# ControllerBoardSchematic.net
KiCad netlist of a schematic drawn in Altium Designer
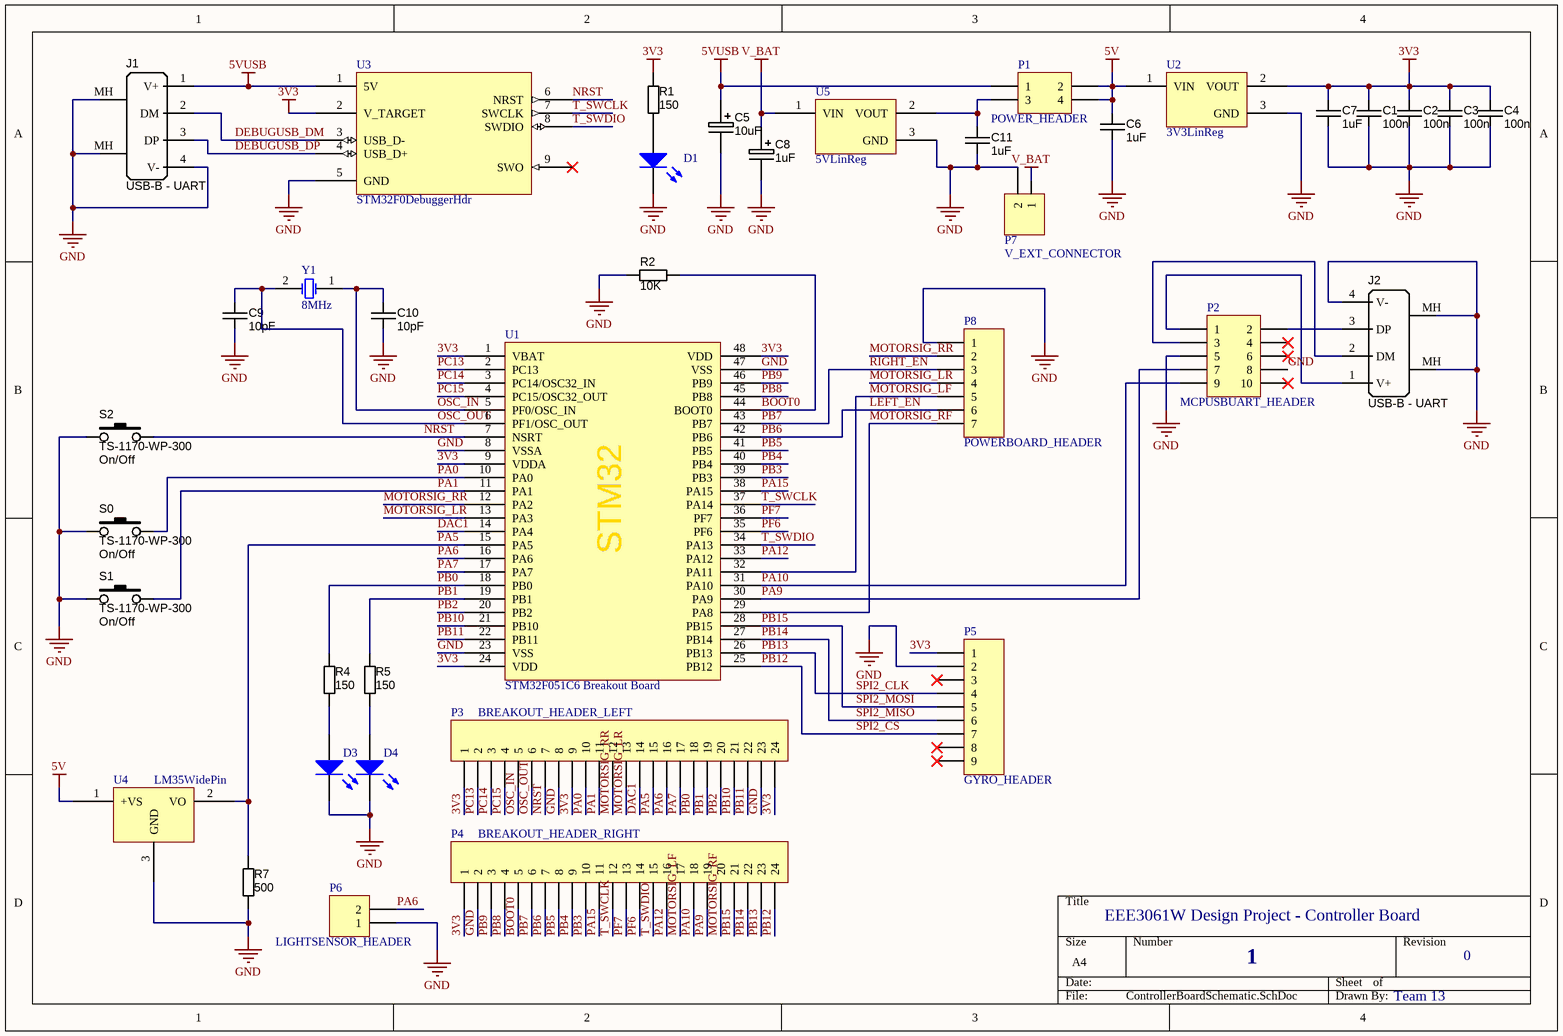
[diagram p0: ControllerBoardSchematic.SchDoc]

(export (version "E")
  (design (tool "Eeschema 10.0.6"))
  (components
    (comp (ref "C1")
      (value "100n")
      (footprint "CAPC500P450250X550_2.5mm")
      (description "Capacitor Ceramic 220nF 10% 50V X7R radial 5mm lead spacing")
      (fields (field (name "TOLERANCE") "±10%"))
      (libsource (lib "PBL - Capacitors") (part "CAPR_220n_Radial_5mm"))
    )
    (comp (ref "C2")
      (value "100n")
      (footprint "CAPC500P450250X550_2.5mm")
      (description "Capacitor Ceramic 220nF 10% 50V X7R radial 5mm lead spacing")
      (fields (field (name "TOLERANCE") "±10%"))
      (libsource (lib "PBL - Capacitors") (part "CAPR_220n_Radial_5mm"))
    )
    (comp (ref "C3")
      (value "100n")
      (footprint "CAPC500P450250X550_2.5mm")
      (description "Capacitor Ceramic 220nF 10% 50V X7R radial 5mm lead spacing")
      (fields (field (name "TOLERANCE") "±10%"))
      (libsource (lib "PBL - Capacitors") (part "CAPR_220n_Radial_5mm"))
    )
    (comp (ref "C4")
      (value "100n")
      (footprint "CAPC500P450250X550_2.5mm")
      (description "Capacitor Ceramic 220nF 10% 50V X7R radial 5mm lead spacing")
      (fields (field (name "TOLERANCE") "±10%"))
      (libsource (lib "PBL - Capacitors") (part "CAPR_220n_Radial_5mm"))
    )
    (comp (ref "C5")
      (value "10uF")
      (footprint "CAPE10.0MM_Rad_10x14mm")
      (description "Capacitor THT Alum Elec 470uF 20% 16V")
      (fields (field (name "TOLERANCE") "±20%"))
      (libsource (lib "PBL - Capacitors") (part "CAPE_470u_16V_THT"))
    )
    (comp (ref "C6")
      (value "1uF")
      (footprint "CAPC500P450250X550_2.5mm")
      (description "Capacitor Ceramic 220nF 10% 50V X7R radial 5mm lead spacing")
      (fields (field (name "TOLERANCE") "±10%"))
      (libsource (lib "PBL - Capacitors") (part "CAPR_220n_Radial_5mm"))
    )
    (comp (ref "C7")
      (value "1uF")
      (footprint "CAPC500P450250X550_2.5mm")
      (description "Capacitor Ceramic 220nF 10% 50V X7R radial 5mm lead spacing")
      (fields (field (name "TOLERANCE") "±10%"))
      (libsource (lib "PBL - Capacitors") (part "CAPR_220n_Radial_5mm"))
    )
    (comp (ref "C8")
      (value "1uF")
      (footprint "CAPE10.0MM_Rad_10x14mm")
      (description "Capacitor THT Alum Elec 470uF 20% 16V")
      (fields (field (name "TOLERANCE") "±20%"))
      (libsource (lib "PBL - Capacitors") (part "CAPE_470u_16V_THT"))
    )
    (comp (ref "C9")
      (value "10pF")
      (footprint "CAPC500P450250X550_2.5mm")
      (description "Capacitor Ceramic 220nF 10% 50V X7R radial 5mm lead spacing")
      (fields (field (name "TOLERANCE") "±10%"))
      (libsource (lib "PBL - Capacitors") (part "CAPR_220n_Radial_5mm"))
    )
    (comp (ref "C10")
      (value "10pF")
      (footprint "CAPC500P450250X550_2.5mm")
      (description "Capacitor Ceramic 220nF 10% 50V X7R radial 5mm lead spacing")
      (fields (field (name "TOLERANCE") "±10%"))
      (libsource (lib "PBL - Capacitors") (part "CAPR_220n_Radial_5mm"))
    )
    (comp (ref "C11")
      (value "1uF")
      (footprint "CAPC500P450250X550_2.5mm")
      (description "Capacitor Ceramic 220nF 10% 50V X7R radial 5mm lead spacing")
      (fields (field (name "TOLERANCE") "±10%"))
      (libsource (lib "PBL - Capacitors") (part "CAPR_220n_Radial_5mm"))
    )
    (comp (ref "D1")
      (value "LED1")
      (footprint "LED-1")
      (description "Typical RED GaAs LED")
      (fields (field (name "PUBLISHER") "Altium Limited"))
      (libsource (lib "Miscellaneous Devices") (part "LED1"))
    )
    (comp (ref "D3")
      (value "LED1")
      (footprint "LED-1")
      (description "Typical RED GaAs LED")
      (fields (field (name "PUBLISHER") "Altium Limited"))
      (libsource (lib "Miscellaneous Devices") (part "LED1"))
    )
    (comp (ref "D4")
      (value "LED1")
      (footprint "LED-1")
      (description "Typical RED GaAs LED")
      (fields (field (name "PUBLISHER") "Altium Limited"))
      (libsource (lib "Miscellaneous Devices") (part "LED1"))
    )
    (comp (ref "J1")
      (value "USB-B - UART")
      (footprint "USB_TypeB_Tyco")
      (description "Connector THT Type B USB connector")
      (libsource (lib "PBL - Connectors") (part "USB_TypeB"))
    )
    (comp (ref "J2")
      (value "USB-B - UART")
      (footprint "USB_TypeB_Tyco")
      (description "Connector THT Type B USB connector")
      (libsource (lib "PBL - Connectors") (part "USB_TypeB"))
    )
    (comp (ref "P1")
      (value "POWER_HEADER")
      (footprint "HDR2X2")
      (description "Header, 2-Pin, Dual row")
      (fields (field (name "PUBLISHER") "Altium Limited"))
      (libsource (lib "Miscellaneous Connectors") (part "Header 2X2"))
    )
    (comp (ref "P2")
      (value "MCPUSBUART_HEADER")
      (footprint "HDR2X5")
      (description "Header, 5-Pin, Dual row")
      (fields (field (name "PUBLISHER") "Altium Limited"))
      (libsource (lib "Miscellaneous Connectors") (part "Header 5X2"))
    )
    (comp (ref "P3")
      (value "BREAKOUT_HEADER_LEFT")
      (footprint "HDR1X24")
      (description "Header, 24-Pin")
      (fields (field (name "PUBLISHER") "Altium Limited"))
      (libsource (lib "Miscellaneous Connectors") (part "Header 24"))
    )
    (comp (ref "P4")
      (value "BREAKOUT_HEADER_RIGHT")
      (footprint "HDR1X24")
      (description "Header, 24-Pin")
      (fields (field (name "PUBLISHER") "Altium Limited"))
      (libsource (lib "Miscellaneous Connectors") (part "Header 24"))
    )
    (comp (ref "P5")
      (value "GYRO_HEADER")
      (footprint "HDR1X9")
      (description "Header, 9-Pin")
      (fields (field (name "PUBLISHER") "Altium Limited"))
      (libsource (lib "Miscellaneous Connectors") (part "Header 9"))
    )
    (comp (ref "P6")
      (value "LIGHTSENSOR_HEADER")
      (footprint "HDR1X2")
      (description "Header, 2-Pin")
      (fields (field (name "PUBLISHER") "Altium Limited"))
      (libsource (lib "") (part "Header 2_1"))
    )
    (comp (ref "P7")
      (value "V_EXT_CONNECTOR")
      (footprint "HDR1X2")
      (description "Header, 2-Pin")
      (fields (field (name "PUBLISHER") "Altium Limited"))
      (libsource (lib "Miscellaneous Connectors") (part "Header 2"))
    )
    (comp (ref "P8")
      (value "POWERBOARD_HEADER")
      (footprint "HDR1X7")
      (description "Header, 7-Pin")
      (fields (field (name "PUBLISHER") "Altium Limited"))
      (libsource (lib "Miscellaneous Connectors") (part "Header 7"))
    )
    (comp (ref "R1")
      (value "150")
      (footprint "RESTH_AXIAL-0.4")
      (description "Resistor THD Axial 1k Ohm 0.25W 5% Carbon Film")
      (fields (field (name "TOLERANCE") "±5%") (field (name "Comment") "Carbon Film"))
      (libsource (lib "PBL - Resistors") (part "RES_1K_Axial_0.25W_5%"))
    )
    (comp (ref "R2")
      (value "10K")
      (footprint "RESTH_AXIAL-0.4")
      (description "Resistor THD Axial 1k Ohm 0.25W 5% Carbon Film")
      (fields (field (name "TOLERANCE") "±5%") (field (name "Comment") "Carbon Film"))
      (libsource (lib "") (part "RES_1K_Axial_0.25W_5%_2"))
    )
    (comp (ref "R4")
      (value "150")
      (footprint "RESTH_AXIAL-0.4")
      (description "Resistor THD Axial 1k Ohm 0.25W 5% Carbon Film")
      (fields (field (name "TOLERANCE") "±5%") (field (name "Comment") "Carbon Film"))
      (libsource (lib "") (part "RES_1K_Axial_0.25W_5%_1"))
    )
    (comp (ref "R5")
      (value "150")
      (footprint "RESTH_AXIAL-0.4")
      (description "Resistor THD Axial 1k Ohm 0.25W 5% Carbon Film")
      (fields (field (name "TOLERANCE") "±5%") (field (name "Comment") "Carbon Film"))
      (libsource (lib "") (part "RES_1K_Axial_0.25W_5%_1"))
    )
    (comp (ref "R7")
      (value "500")
      (footprint "RESTH_AXIAL-0.4")
      (description "Resistor THD Axial 1k Ohm 0.25W 5% Carbon Film")
      (fields (field (name "TOLERANCE") "±5%") (field (name "Comment") "Carbon Film"))
      (libsource (lib "") (part "RES_1K_Axial_0.25W_5%_1"))
    )
    (comp (ref "S0")
      (value "SW_THT_PB_7.0mm")
      (footprint "TACT-SWITCH-TS1170")
      (description "Switch, tact, 7.0mm stem")
      (fields (field (name "MANUFACTURER PART NUMBER 1") "TS-1170-WP-300") (field (name "FUNCTION") "On/Off"))
      (libsource (lib "PBL - Switches") (part "SW_THT_PB_7.0mm"))
    )
    (comp (ref "S1")
      (value "SW_THT_PB_7.0mm")
      (footprint "TACT-SWITCH-TS1170")
      (description "Switch, tact, 7.0mm stem")
      (fields (field (name "MANUFACTURER PART NUMBER 1") "TS-1170-WP-300") (field (name "FUNCTION") "On/Off"))
      (libsource (lib "PBL - Switches") (part "SW_THT_PB_7.0mm"))
    )
    (comp (ref "S2")
      (value "SW_THT_PB_7.0mm")
      (footprint "TACT-SWITCH-TS1170")
      (description "Switch, tact, 7.0mm stem")
      (fields (field (name "MANUFACTURER PART NUMBER 1") "TS-1170-WP-300") (field (name "FUNCTION") "On/Off"))
      (libsource (lib "PBL - Switches") (part "SW_THT_PB_7.0mm"))
    )
    (comp (ref "U1")
      (value "STM32F051C6 Breakout Board")
      (footprint "STM32F051C6BreakoutBoard")
      (libsource (lib "STM32F051C6Breakout") (part "STM32F051C6Brk"))
    )
    (comp (ref "U2")
      (value "3V3LinReg")
      (footprint "TO-92Wide")
      (description "MCP")
      (libsource (lib "STM32F051C6Breakout") (part "VREG5V"))
    )
    (comp (ref "U3")
      (value "STM32F0DebuggerHdr")
      (footprint "STM32F051C6_DbgrHdr")
      (libsource (lib "STM32F051C6Breakout") (part "STM32F0DebuggerHdr"))
    )
    (comp (ref "U4")
      (value "LM35WidePin")
      (footprint "TO-92Wide")
      (libsource (lib "STM32F051C6Breakout") (part "LM35Big"))
    )
    (comp (ref "U5")
      (value "5VLinReg")
      (footprint "TO-92Wide")
      (description "MCP")
      (libsource (lib "STM32F051C6Breakout") (part "VREG5V"))
    )
    (comp (ref "Y1")
      (value "8MHz")
      (footprint "8MHZOSC")
      (description "Crystal Oscillator")
      (fields (field (name "PUBLISHER") "Altium Limited"))
      (libsource (lib "Miscellaneous Devices") (part "XTAL"))
    )
  )
  (nets
    (net (code "1") (name "/BOOT0") (class "Default")
      (node (ref "P4") (pin "5") (pinfunction "5_5") (pintype "passive"))
      (node (ref "R2") (pin "2") (pinfunction "2_2") (pintype "passive"))
      (node (ref "U1") (pin "44") (pinfunction "BOOT0_44") (pintype "passive"))
    )
    (net (code "2") (name "/DAC1") (class "Default")
      (node (ref "P3") (pin "14") (pinfunction "14_14") (pintype "passive"))
      (node (ref "U1") (pin "14") (pinfunction "PA4_14") (pintype "passive"))
    )
    (net (code "3") (name "/DEBUGUSB_DM") (class "Default")
      (node (ref "J1") (pin "2") (pinfunction "DM_2") (pintype "passive"))
      (node (ref "U3") (pin "3") (pinfunction "USB_D-_3") (pintype "bidirectional"))
    )
    (net (code "4") (name "/DEBUGUSB_DP") (class "Default")
      (node (ref "J1") (pin "3") (pinfunction "DP_3") (pintype "passive"))
      (node (ref "U3") (pin "4") (pinfunction "USB_D+_4") (pintype "bidirectional"))
    )
    (net (code "5") (name "/LEFT_EN") (class "Default")
      (node (ref "P4") (pin "7") (pinfunction "7_7") (pintype "passive"))
      (node (ref "P8") (pin "6") (pinfunction "6_6") (pintype "passive"))
      (node (ref "U1") (pin "42") (pinfunction "PB6_42") (pintype "passive"))
    )
    (net (code "6") (name "/MOTORSIG_LF") (class "Default")
      (node (ref "P4") (pin "17") (pinfunction "17_17") (pintype "passive"))
      (node (ref "P8") (pin "5") (pinfunction "5_5") (pintype "passive"))
      (node (ref "U1") (pin "32") (pinfunction "PA11_32") (pintype "passive"))
    )
    (net (code "7") (name "/MOTORSIG_LR") (class "Default")
      (node (ref "P3") (pin "13") (pinfunction "13_13") (pintype "passive"))
      (node (ref "P8") (pin "4") (pinfunction "4_4") (pintype "passive"))
      (node (ref "U1") (pin "13") (pinfunction "PA3_13") (pintype "passive"))
    )
    (net (code "8") (name "/MOTORSIG_RF") (class "Default")
      (node (ref "P4") (pin "20") (pinfunction "20_20") (pintype "passive"))
      (node (ref "P8") (pin "7") (pinfunction "7_7") (pintype "passive"))
      (node (ref "U1") (pin "29") (pinfunction "PA8_29") (pintype "passive"))
    )
    (net (code "9") (name "/MOTORSIG_RR") (class "Default")
      (node (ref "P3") (pin "12") (pinfunction "12_12") (pintype "passive"))
      (node (ref "P8") (pin "2") (pinfunction "2_2") (pintype "passive"))
      (node (ref "U1") (pin "12") (pinfunction "PA2_12") (pintype "passive"))
    )
    (net (code "10") (name "/NRST") (class "Default")
      (node (ref "P3") (pin "7") (pinfunction "7_7") (pintype "passive"))
      (node (ref "S2") (pin "2") (pintype "passive"))
      (node (ref "U1") (pin "7") (pinfunction "NSRT_7") (pintype "passive"))
      (node (ref "U3") (pin "6") (pinfunction "NRST_6") (pintype "output"))
    )
    (net (code "11") (name "/OSC_IN") (class "Default")
      (node (ref "C10") (pin "1") (pintype "passive"))
      (node (ref "P3") (pin "5") (pinfunction "5_5") (pintype "passive"))
      (node (ref "U1") (pin "5") (pinfunction "PF0/OSC_IN_5") (pintype "passive"))
      (node (ref "Y1") (pin "1") (pinfunction "OSC1_1") (pintype "passive"))
    )
    (net (code "12") (name "/OSC_OUT") (class "Default")
      (node (ref "C9") (pin "1") (pintype "passive"))
      (node (ref "P3") (pin "6") (pinfunction "6_6") (pintype "passive"))
      (node (ref "U1") (pin "6") (pinfunction "PF1/OSC_OUT_6") (pintype "passive"))
      (node (ref "Y1") (pin "2") (pinfunction "OSC2_2") (pintype "passive"))
    )
    (net (code "13") (name "/PA0") (class "Default")
      (node (ref "P3") (pin "10") (pinfunction "10_10") (pintype "passive"))
      (node (ref "S0") (pin "2") (pintype "passive"))
      (node (ref "U1") (pin "10") (pinfunction "PA0_10") (pintype "passive"))
    )
    (net (code "14") (name "/PA1") (class "Default")
      (node (ref "P3") (pin "11") (pinfunction "11_11") (pintype "passive"))
      (node (ref "S1") (pin "2") (pintype "passive"))
      (node (ref "U1") (pin "11") (pinfunction "PA1_11") (pintype "passive"))
    )
    (net (code "15") (name "/PA5") (class "Default")
      (node (ref "P3") (pin "15") (pinfunction "15_15") (pintype "passive"))
      (node (ref "R7") (pin "1") (pinfunction "1_1") (pintype "passive"))
      (node (ref "U1") (pin "15") (pinfunction "PA5_15") (pintype "passive"))
      (node (ref "U4") (pin "2") (pinfunction "VO_2") (pintype "passive"))
    )
    (net (code "16") (name "/PA6") (class "Default")
      (node (ref "P3") (pin "16") (pinfunction "16_16") (pintype "passive"))
      (node (ref "P6") (pin "2") (pinfunction "2_2") (pintype "passive"))
      (node (ref "U1") (pin "16") (pinfunction "PA6_16") (pintype "passive"))
    )
    (net (code "17") (name "/PA7") (class "Default")
      (node (ref "P3") (pin "17") (pinfunction "17_17") (pintype "passive"))
      (node (ref "U1") (pin "17") (pinfunction "PA7_17") (pintype "passive"))
    )
    (net (code "18") (name "/PA9") (class "Default")
      (node (ref "P2") (pin "7") (pinfunction "7_7") (pintype "passive"))
      (node (ref "P4") (pin "19") (pinfunction "19_19") (pintype "passive"))
      (node (ref "U1") (pin "30") (pinfunction "PA9_30") (pintype "passive"))
    )
    (net (code "19") (name "/PA10") (class "Default")
      (node (ref "P2") (pin "9") (pinfunction "9_9") (pintype "passive"))
      (node (ref "P4") (pin "18") (pinfunction "18_18") (pintype "passive"))
      (node (ref "U1") (pin "31") (pinfunction "PA10_31") (pintype "passive"))
    )
    (net (code "20") (name "/PA12") (class "Default")
      (node (ref "P4") (pin "16") (pinfunction "16_16") (pintype "passive"))
      (node (ref "U1") (pin "33") (pinfunction "PA12_33") (pintype "passive"))
    )
    (net (code "21") (name "/PA15") (class "Default")
      (node (ref "P4") (pin "11") (pinfunction "11_11") (pintype "passive"))
      (node (ref "U1") (pin "38") (pinfunction "PA15_38") (pintype "passive"))
    )
    (net (code "22") (name "/PB0") (class "Default")
      (node (ref "P3") (pin "18") (pinfunction "18_18") (pintype "passive"))
      (node (ref "R4") (pin "1") (pinfunction "1_1") (pintype "passive"))
      (node (ref "U1") (pin "18") (pinfunction "PB0_18") (pintype "passive"))
    )
    (net (code "23") (name "/PB1") (class "Default")
      (node (ref "P3") (pin "19") (pinfunction "19_19") (pintype "passive"))
      (node (ref "R5") (pin "1") (pinfunction "1_1") (pintype "passive"))
      (node (ref "U1") (pin "19") (pinfunction "PB1_19") (pintype "passive"))
    )
    (net (code "24") (name "/PB2") (class "Default")
      (node (ref "P3") (pin "20") (pinfunction "20_20") (pintype "passive"))
      (node (ref "U1") (pin "20") (pinfunction "PB2_20") (pintype "passive"))
    )
    (net (code "25") (name "/PB3") (class "Default")
      (node (ref "P4") (pin "10") (pinfunction "10_10") (pintype "passive"))
      (node (ref "U1") (pin "39") (pinfunction "PB3_39") (pintype "passive"))
    )
    (net (code "26") (name "/PB4") (class "Default")
      (node (ref "P4") (pin "9") (pinfunction "9_9") (pintype "passive"))
      (node (ref "U1") (pin "40") (pinfunction "PB4_40") (pintype "passive"))
    )
    (net (code "27") (name "/PB5") (class "Default")
      (node (ref "P4") (pin "8") (pinfunction "8_8") (pintype "passive"))
      (node (ref "U1") (pin "41") (pinfunction "PB5_41") (pintype "passive"))
    )
    (net (code "28") (name "/PB7") (class "Default")
      (node (ref "P4") (pin "6") (pinfunction "6_6") (pintype "passive"))
      (node (ref "P8") (pin "3") (pinfunction "3_3") (pintype "passive"))
      (node (ref "U1") (pin "43") (pinfunction "PB7_43") (pintype "passive"))
    )
    (net (code "29") (name "/PB8") (class "Default")
      (node (ref "P4") (pin "4") (pinfunction "4_4") (pintype "passive"))
      (node (ref "U1") (pin "45") (pinfunction "PB8_45") (pintype "passive"))
    )
    (net (code "30") (name "/PB9") (class "Default")
      (node (ref "P4") (pin "3") (pinfunction "3_3") (pintype "passive"))
      (node (ref "U1") (pin "46") (pinfunction "PB9_46") (pintype "passive"))
    )
    (net (code "31") (name "/PB10") (class "Default")
      (node (ref "P3") (pin "21") (pinfunction "21_21") (pintype "passive"))
      (node (ref "U1") (pin "21") (pinfunction "PB10_21") (pintype "passive"))
    )
    (net (code "32") (name "/PB11") (class "Default")
      (node (ref "P3") (pin "22") (pinfunction "22_22") (pintype "passive"))
      (node (ref "U1") (pin "22") (pinfunction "PB11_22") (pintype "passive"))
    )
    (net (code "33") (name "/PB12") (class "Default")
      (node (ref "P4") (pin "24") (pinfunction "24_24") (pintype "passive"))
      (node (ref "P5") (pin "7") (pinfunction "7_7") (pintype "passive"))
      (node (ref "U1") (pin "25") (pinfunction "PB12_25") (pintype "passive"))
    )
    (net (code "34") (name "/PB13") (class "Default")
      (node (ref "P4") (pin "23") (pinfunction "23_23") (pintype "passive"))
      (node (ref "P5") (pin "4") (pinfunction "4_4") (pintype "passive"))
      (node (ref "U1") (pin "26") (pinfunction "PB13_26") (pintype "passive"))
    )
    (net (code "35") (name "/PB14") (class "Default")
      (node (ref "P4") (pin "22") (pinfunction "22_22") (pintype "passive"))
      (node (ref "P5") (pin "6") (pinfunction "6_6") (pintype "passive"))
      (node (ref "U1") (pin "27") (pinfunction "PB14_27") (pintype "passive"))
    )
    (net (code "36") (name "/PB15") (class "Default")
      (node (ref "P4") (pin "21") (pinfunction "21_21") (pintype "passive"))
      (node (ref "P5") (pin "5") (pinfunction "5_5") (pintype "passive"))
      (node (ref "U1") (pin "28") (pinfunction "PB15_28") (pintype "passive"))
    )
    (net (code "37") (name "/PC13") (class "Default")
      (node (ref "P3") (pin "2") (pinfunction "2_2") (pintype "passive"))
      (node (ref "U1") (pin "2") (pinfunction "PC13_2") (pintype "passive"))
    )
    (net (code "38") (name "/PC14") (class "Default")
      (node (ref "P3") (pin "3") (pinfunction "3_3") (pintype "passive"))
      (node (ref "U1") (pin "3") (pinfunction "PC14/OSC32_IN_3") (pintype "passive"))
    )
    (net (code "39") (name "/PC15") (class "Default")
      (node (ref "P3") (pin "4") (pinfunction "4_4") (pintype "passive"))
      (node (ref "U1") (pin "4") (pinfunction "PC15/OSC32_OUT_4") (pintype "passive"))
    )
    (net (code "40") (name "/PF6") (class "Default")
      (node (ref "P4") (pin "14") (pinfunction "14_14") (pintype "passive"))
      (node (ref "U1") (pin "35") (pinfunction "PF6_35") (pintype "passive"))
    )
    (net (code "41") (name "/PF7") (class "Default")
      (node (ref "P4") (pin "13") (pinfunction "13_13") (pintype "passive"))
      (node (ref "U1") (pin "36") (pinfunction "PF7_36") (pintype "passive"))
    )
    (net (code "42") (name "/T_SWCLK") (class "Default")
      (node (ref "P4") (pin "12") (pinfunction "12_12") (pintype "passive"))
      (node (ref "U1") (pin "37") (pinfunction "PA14_37") (pintype "passive"))
      (node (ref "U3") (pin "7") (pinfunction "SWCLK_7") (pintype "output"))
    )
    (net (code "43") (name "/T_SWDIO") (class "Default")
      (node (ref "P4") (pin "15") (pinfunction "15_15") (pintype "passive"))
      (node (ref "U1") (pin "34") (pinfunction "PA13_34") (pintype "passive"))
      (node (ref "U3") (pin "8") (pinfunction "SWDIO_8") (pintype "bidirectional"))
    )
    (net (code "44") (name "3V3") (class "Default")
      (node (ref "C1") (pin "1") (pintype "passive"))
      (node (ref "C2") (pin "1") (pintype "passive"))
      (node (ref "C3") (pin "1") (pintype "passive"))
      (node (ref "C4") (pin "1") (pintype "passive"))
      (node (ref "C7") (pin "1") (pintype "passive"))
      (node (ref "P3") (pin "1") (pinfunction "1_1") (pintype "passive"))
      (node (ref "P3") (pin "24") (pinfunction "24_24") (pintype "passive"))
      (node (ref "P3") (pin "9") (pinfunction "9_9") (pintype "passive"))
      (node (ref "P4") (pin "1") (pinfunction "1_1") (pintype "passive"))
      (node (ref "P5") (pin "1") (pinfunction "1_1") (pintype "passive"))
      (node (ref "R1") (pin "2") (pinfunction "2_2") (pintype "passive"))
      (node (ref "U1") (pin "1") (pinfunction "VBAT_1") (pintype "passive"))
      (node (ref "U1") (pin "24") (pinfunction "VDD_24") (pintype "passive"))
      (node (ref "U1") (pin "48") (pinfunction "VDD_48") (pintype "passive"))
      (node (ref "U1") (pin "9") (pinfunction "VDDA_9") (pintype "passive"))
      (node (ref "U2") (pin "2") (pinfunction "VOUT_2") (pintype "passive"))
      (node (ref "U3") (pin "2") (pinfunction "V_TARGET_2") (pintype "passive"))
    )
    (net (code "45") (name "5V") (class "Default")
      (node (ref "C6") (pin "1") (pintype "passive"))
      (node (ref "P1") (pin "2") (pinfunction "2_2") (pintype "passive"))
      (node (ref "P1") (pin "4") (pinfunction "4_4") (pintype "passive"))
      (node (ref "U2") (pin "1") (pinfunction "VIN_1") (pintype "passive"))
      (node (ref "U4") (pin "1") (pinfunction "+VS_1") (pintype "passive"))
    )
    (net (code "46") (name "5VUSB") (class "Default")
      (node (ref "C5") (pin "1") (pintype "passive"))
      (node (ref "J1") (pin "1") (pinfunction "V+_1") (pintype "passive"))
      (node (ref "P1") (pin "1") (pinfunction "1_1") (pintype "passive"))
      (node (ref "U3") (pin "1") (pinfunction "5V_1") (pintype "passive"))
    )
    (net (code "47") (name "GND") (class "Default")
      (node (ref "C1") (pin "2") (pintype "passive"))
      (node (ref "C10") (pin "2") (pintype "passive"))
      (node (ref "C11") (pin "2") (pintype "passive"))
      (node (ref "C2") (pin "2") (pintype "passive"))
      (node (ref "C3") (pin "2") (pintype "passive"))
      (node (ref "C4") (pin "2") (pintype "passive"))
      (node (ref "C5") (pin "2") (pintype "passive"))
      (node (ref "C6") (pin "2") (pintype "passive"))
      (node (ref "C7") (pin "2") (pintype "passive"))
      (node (ref "C8") (pin "2") (pintype "passive"))
      (node (ref "C9") (pin "2") (pintype "passive"))
      (node (ref "D1") (pin "2") (pinfunction "K_2") (pintype "passive"))
      (node (ref "D3") (pin "2") (pinfunction "K_2") (pintype "passive"))
      (node (ref "D4") (pin "2") (pinfunction "K_2") (pintype "passive"))
      (node (ref "J1") (pin "4") (pinfunction "V-_4") (pintype "passive"))
      (node (ref "J1") (pin "MH") (pinfunction "Shell_MH") (pintype "passive"))
      (node (ref "J2") (pin "4") (pinfunction "V-_4") (pintype "passive"))
      (node (ref "J2") (pin "MH") (pinfunction "Shell_MH") (pintype "passive"))
      (node (ref "P2") (pin "5") (pinfunction "5_5") (pintype "passive"))
      (node (ref "P2") (pin "8") (pinfunction "8_8") (pintype "passive"))
      (node (ref "P3") (pin "23") (pinfunction "23_23") (pintype "passive"))
      (node (ref "P3") (pin "8") (pinfunction "8_8") (pintype "passive"))
      (node (ref "P4") (pin "2") (pinfunction "2_2") (pintype "passive"))
      (node (ref "P5") (pin "2") (pinfunction "2_2") (pintype "passive"))
      (node (ref "P6") (pin "1") (pinfunction "1_1") (pintype "passive"))
      (node (ref "P7") (pin "2") (pinfunction "2_2") (pintype "passive"))
      (node (ref "P8") (pin "1") (pinfunction "1_1") (pintype "passive"))
      (node (ref "R2") (pin "1") (pinfunction "1_1") (pintype "passive"))
      (node (ref "R7") (pin "2") (pinfunction "2_2") (pintype "passive"))
      (node (ref "S0") (pin "1") (pintype "passive"))
      (node (ref "S1") (pin "1") (pintype "passive"))
      (node (ref "S2") (pin "1") (pintype "passive"))
      (node (ref "U1") (pin "23") (pinfunction "VSS_23") (pintype "passive"))
      (node (ref "U1") (pin "47") (pinfunction "VSS_47") (pintype "passive"))
      (node (ref "U1") (pin "8") (pinfunction "VSSA_8") (pintype "passive"))
      (node (ref "U2") (pin "3") (pinfunction "GND_3") (pintype "passive"))
      (node (ref "U3") (pin "5") (pinfunction "GND_5") (pintype "passive"))
      (node (ref "U4") (pin "3") (pinfunction "GND_3") (pintype "passive"))
      (node (ref "U5") (pin "3") (pinfunction "GND_3") (pintype "passive"))
    )
    (net (code "48") (name "Net-(D1-A)") (class "Default")
      (node (ref "D1") (pin "1") (pinfunction "A_1") (pintype "passive"))
      (node (ref "R1") (pin "1") (pinfunction "1_1") (pintype "passive"))
    )
    (net (code "49") (name "Net-(D3-A)") (class "Default")
      (node (ref "D3") (pin "1") (pinfunction "A_1") (pintype "passive"))
      (node (ref "R4") (pin "2") (pinfunction "2_2") (pintype "passive"))
    )
    (net (code "50") (name "Net-(D4-A)") (class "Default")
      (node (ref "D4") (pin "1") (pinfunction "A_1") (pintype "passive"))
      (node (ref "R5") (pin "2") (pinfunction "2_2") (pintype "passive"))
    )
    (net (code "51") (name "Net-(J2-DM)") (class "Default")
      (node (ref "J2") (pin "2") (pinfunction "DM_2") (pintype "passive"))
      (node (ref "P2") (pin "3") (pinfunction "3_3") (pintype "passive"))
    )
    (net (code "52") (name "Net-(J2-DP)") (class "Default")
      (node (ref "J2") (pin "3") (pinfunction "DP_3") (pintype "passive"))
      (node (ref "P2") (pin "2") (pinfunction "2_2") (pintype "passive"))
    )
    (net (code "53") (name "Net-(J2-V+)") (class "Default")
      (node (ref "J2") (pin "1") (pinfunction "V+_1") (pintype "passive"))
      (node (ref "P2") (pin "1") (pinfunction "1_1") (pintype "passive"))
    )
    (net (code "54") (name "Net-(U5-VOUT)") (class "Default")
      (node (ref "C11") (pin "1") (pintype "passive"))
      (node (ref "P1") (pin "3") (pinfunction "3_3") (pintype "passive"))
      (node (ref "U5") (pin "2") (pinfunction "VOUT_2") (pintype "passive"))
    )
    (net (code "55") (name "V_BAT") (class "Default")
      (node (ref "C8") (pin "1") (pintype "passive"))
      (node (ref "P7") (pin "1") (pinfunction "1_1") (pintype "passive"))
      (node (ref "U5") (pin "1") (pinfunction "VIN_1") (pintype "passive"))
    )
    (net (code "56") (name "unconnected-(P2-Pad4)") (class "Default")
      (node (ref "P2") (pin "4") (pinfunction "4_4") (pintype "passive+no_connect"))
    )
    (net (code "57") (name "unconnected-(P2-Pad6)") (class "Default")
      (node (ref "P2") (pin "6") (pinfunction "6_6") (pintype "passive+no_connect"))
    )
    (net (code "58") (name "unconnected-(P2-Pad10)") (class "Default")
      (node (ref "P2") (pin "10") (pinfunction "10_10") (pintype "passive+no_connect"))
    )
    (net (code "59") (name "unconnected-(P5-Pad3)") (class "Default")
      (node (ref "P5") (pin "3") (pinfunction "3_3") (pintype "passive+no_connect"))
    )
    (net (code "60") (name "unconnected-(P5-Pad8)") (class "Default")
      (node (ref "P5") (pin "8") (pinfunction "8_8") (pintype "passive+no_connect"))
    )
    (net (code "61") (name "unconnected-(P5-Pad9)") (class "Default")
      (node (ref "P5") (pin "9") (pinfunction "9_9") (pintype "passive+no_connect"))
    )
    (net (code "62") (name "unconnected-(U3-SWO-Pad9)") (class "Default")
      (node (ref "U3") (pin "9") (pinfunction "SWO_9") (pintype "input+no_connect"))
    )
  )
)
